# esplash.net
KiCad netlist of a schematic drawn in EAGLE
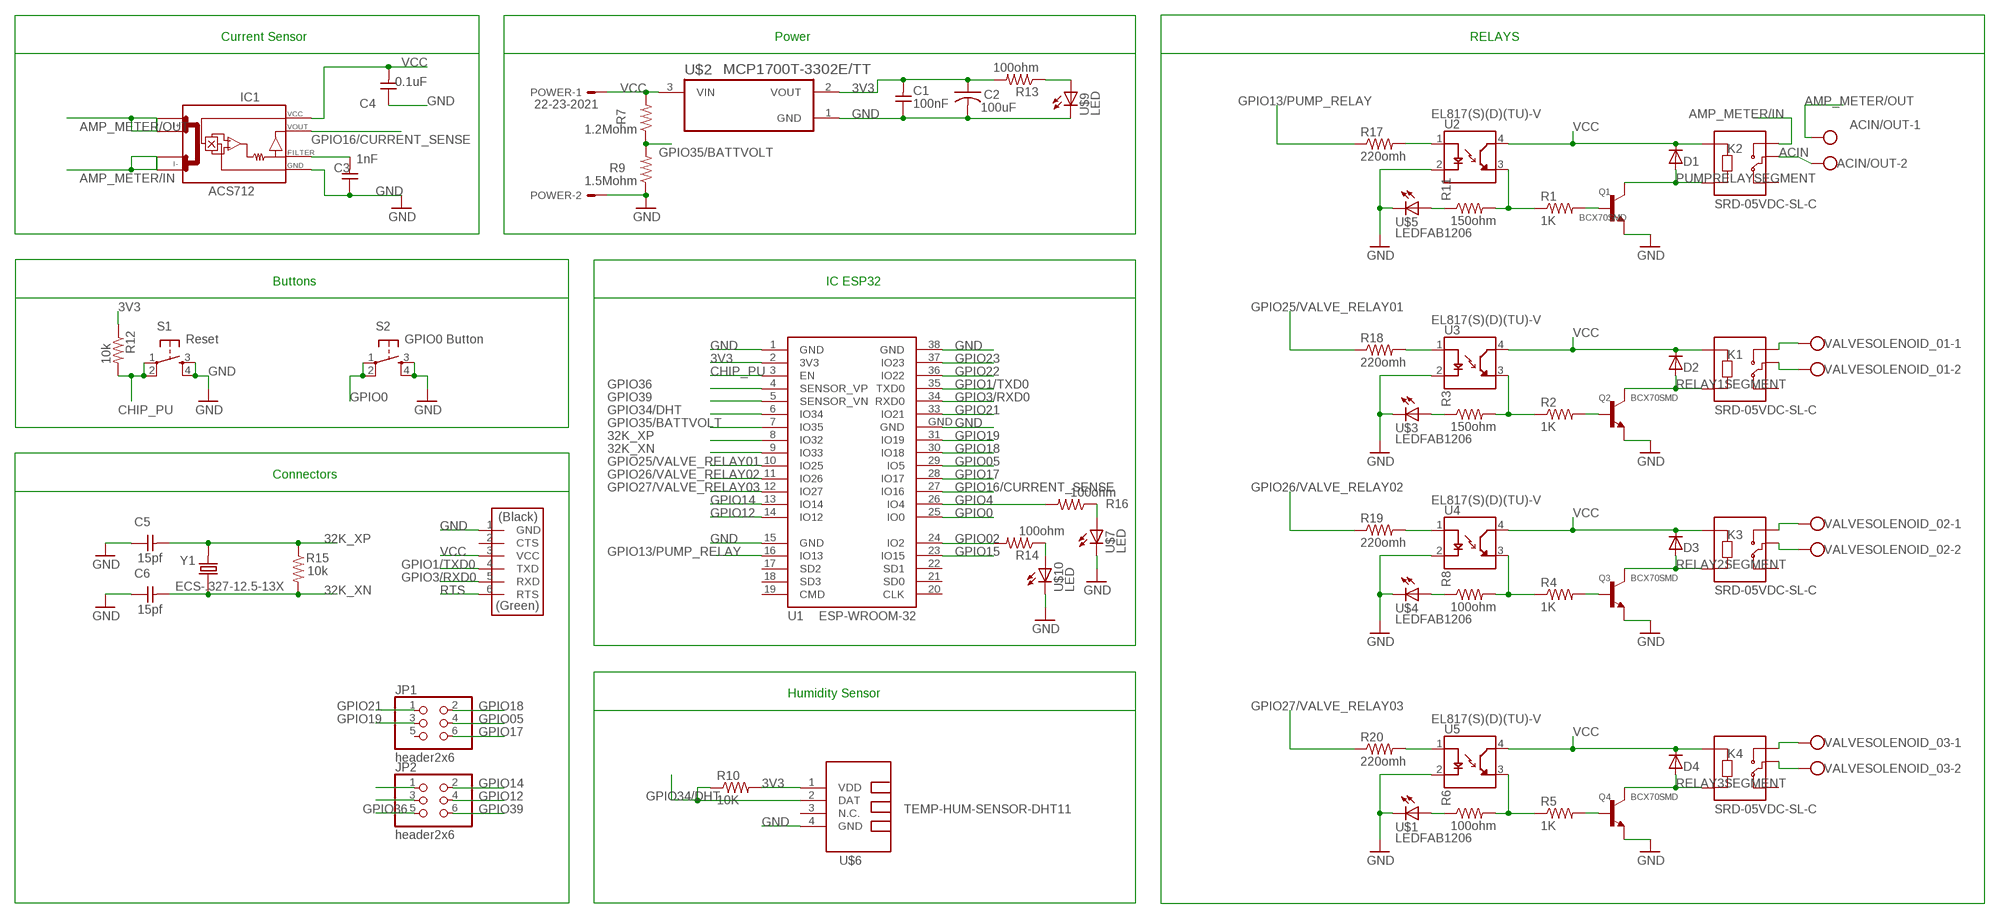
[diagram p0: schematic, sheet 1]

(export (version "E")
  (design (tool "Eeschema 10.0.6"))
  (components
    (comp (ref "ACIN/OUT")
      (value "W237-102")
      (footprint "eagle-import:W237-102")
      (fields (field (name "MPN") "237-102"))
      (libsource (lib "eagle-import") (part "W237-102"))
    )
    (comp (ref "C1")
      (value "100nF")
      (footprint "eagle-import:C1206FAB")
      (libsource (lib "eagle-import") (part "CAP-UNPOLARIZEDFAB"))
    )
    (comp (ref "C2")
      (value "100uF")
      (footprint "eagle-import:C1206FAB")
      (libsource (lib "eagle-import") (part "CAP-US1206FAB"))
    )
    (comp (ref "C3")
      (value "1nF")
      (footprint "eagle-import:C1206FAB")
      (libsource (lib "eagle-import") (part "CAP-UNPOLARIZEDFAB"))
    )
    (comp (ref "C4")
      (value "0.1uF")
      (footprint "eagle-import:C1206FAB")
      (libsource (lib "eagle-import") (part "CAP-UNPOLARIZEDFAB"))
    )
    (comp (ref "C5")
      (value "15pf")
      (footprint "eagle-import:C1206FAB")
      (libsource (lib "eagle-import") (part "CAP-UNPOLARIZEDFAB"))
    )
    (comp (ref "C6")
      (value "15pf")
      (footprint "eagle-import:C1206FAB")
      (libsource (lib "eagle-import") (part "CAP-UNPOLARIZEDFAB"))
    )
    (comp (ref "D1")
      (value "DIODESOD123")
      (footprint "eagle-import:SOD123")
      (libsource (lib "eagle-import") (part "DIODESOD123"))
    )
    (comp (ref "D2")
      (value "DIODESOD123")
      (footprint "eagle-import:SOD123")
      (libsource (lib "eagle-import") (part "DIODESOD123"))
    )
    (comp (ref "D3")
      (value "DIODESOD123")
      (footprint "eagle-import:SOD123")
      (libsource (lib "eagle-import") (part "DIODESOD123"))
    )
    (comp (ref "D4")
      (value "DIODESOD123")
      (footprint "eagle-import:SOD123")
      (libsource (lib "eagle-import") (part "DIODESOD123"))
    )
    (comp (ref "IC1")
      (value "ACS712")
      (footprint "eagle-import:SO08")
      (libsource (lib "eagle-import") (part "ACS712"))
    )
    (comp (ref "JP1")
      (value "header2x6")
      (footprint "eagle-import:2X03")
      (libsource (lib "eagle-import") (part "PINHD-2X3"))
    )
    (comp (ref "JP2")
      (value "header2x6")
      (footprint "eagle-import:2X03")
      (libsource (lib "eagle-import") (part "PINHD-2X3"))
    )
    (comp (ref "K1")
      (value "SRD-05VDC-SL-C")
      (footprint "eagle-import:RELAY_SRD-05VDC-SL-C")
      (fields (field (name "MF") "Songle Relay"))
      (libsource (lib "eagle-import") (part "SRD-05VDC-SL-C"))
    )
    (comp (ref "K2")
      (value "SRD-05VDC-SL-C")
      (footprint "eagle-import:RELAY_SRD-05VDC-SL-C")
      (fields (field (name "MF") "Songle Relay"))
      (libsource (lib "eagle-import") (part "SRD-05VDC-SL-C"))
    )
    (comp (ref "K3")
      (value "SRD-05VDC-SL-C")
      (footprint "eagle-import:RELAY_SRD-05VDC-SL-C")
      (fields (field (name "MF") "Songle Relay"))
      (libsource (lib "eagle-import") (part "SRD-05VDC-SL-C"))
    )
    (comp (ref "K4")
      (value "SRD-05VDC-SL-C")
      (footprint "eagle-import:RELAY_SRD-05VDC-SL-C")
      (fields (field (name "MF") "Songle Relay"))
      (libsource (lib "eagle-import") (part "SRD-05VDC-SL-C"))
    )
    (comp (ref "POWER")
      (value "22-23-2021")
      (footprint "eagle-import:22-23-2021")
      (fields (field (name "MF") "MOLEX"))
      (libsource (lib "eagle-import") (part "22-23-2021"))
    )
    (comp (ref "Q1")
      (value "BCX70SMD")
      (footprint "eagle-import:SOT23")
      (libsource (lib "eagle-import") (part "BCX70SMD"))
    )
    (comp (ref "Q2")
      (value "BCX70SMD")
      (footprint "eagle-import:SOT23")
      (libsource (lib "eagle-import") (part "BCX70SMD"))
    )
    (comp (ref "Q3")
      (value "BCX70SMD")
      (footprint "eagle-import:SOT23")
      (libsource (lib "eagle-import") (part "BCX70SMD"))
    )
    (comp (ref "Q4")
      (value "BCX70SMD")
      (footprint "eagle-import:SOT23")
      (libsource (lib "eagle-import") (part "BCX70SMD"))
    )
    (comp (ref "R1")
      (value "1K")
      (footprint "eagle-import:R1206FAB")
      (libsource (lib "eagle-import") (part "RES-US1206FAB"))
    )
    (comp (ref "R2")
      (value "1K")
      (footprint "eagle-import:R1206FAB")
      (libsource (lib "eagle-import") (part "RES-US1206FAB"))
    )
    (comp (ref "R3")
      (value "150ohm")
      (footprint "eagle-import:R1206FAB")
      (libsource (lib "eagle-import") (part "RES-US1206FAB"))
    )
    (comp (ref "R4")
      (value "1K")
      (footprint "eagle-import:R1206FAB")
      (libsource (lib "eagle-import") (part "RES-US1206FAB"))
    )
    (comp (ref "R5")
      (value "1K")
      (footprint "eagle-import:R1206FAB")
      (libsource (lib "eagle-import") (part "RES-US1206FAB"))
    )
    (comp (ref "R6")
      (value "100ohm")
      (footprint "eagle-import:R1206FAB")
      (libsource (lib "eagle-import") (part "RES-US1206FAB"))
    )
    (comp (ref "R7")
      (value "1.2Mohm")
      (footprint "eagle-import:R1206FAB")
      (libsource (lib "eagle-import") (part "RES-US1206FAB"))
    )
    (comp (ref "R8")
      (value "100ohm")
      (footprint "eagle-import:R1206FAB")
      (libsource (lib "eagle-import") (part "RES-US1206FAB"))
    )
    (comp (ref "R9")
      (value "1.5Mohm")
      (footprint "eagle-import:R1206FAB")
      (libsource (lib "eagle-import") (part "RES-US1206FAB"))
    )
    (comp (ref "R10")
      (value "10K")
      (footprint "eagle-import:R1206FAB")
      (libsource (lib "eagle-import") (part "RES-US1206FAB"))
    )
    (comp (ref "R11")
      (value "150ohm")
      (footprint "eagle-import:R1206FAB")
      (libsource (lib "eagle-import") (part "RES-US1206FAB"))
    )
    (comp (ref "R12")
      (value "10k")
      (footprint "eagle-import:R1206")
      (libsource (lib "eagle-import") (part "RES-US1206"))
    )
    (comp (ref "R13")
      (value "100ohm")
      (footprint "eagle-import:R1206")
      (libsource (lib "eagle-import") (part "RES-US1206"))
    )
    (comp (ref "R14")
      (value "100ohm")
      (footprint "eagle-import:R1206")
      (libsource (lib "eagle-import") (part "RES-US1206"))
    )
    (comp (ref "R15")
      (value "10k")
      (footprint "eagle-import:R1206")
      (libsource (lib "eagle-import") (part "RES-US1206"))
    )
    (comp (ref "R16")
      (value "100ohm")
      (footprint "eagle-import:R1206")
      (libsource (lib "eagle-import") (part "RES-US1206"))
    )
    (comp (ref "R17")
      (value "220omh")
      (footprint "eagle-import:R1206FAB")
      (libsource (lib "eagle-import") (part "RES-US1206FAB"))
    )
    (comp (ref "R18")
      (value "220omh")
      (footprint "eagle-import:R1206FAB")
      (libsource (lib "eagle-import") (part "RES-US1206FAB"))
    )
    (comp (ref "R19")
      (value "220omh")
      (footprint "eagle-import:R1206FAB")
      (libsource (lib "eagle-import") (part "RES-US1206FAB"))
    )
    (comp (ref "R20")
      (value "220omh")
      (footprint "eagle-import:R1206FAB")
      (libsource (lib "eagle-import") (part "RES-US1206FAB"))
    )
    (comp (ref "RTS")
      (value "FTDI-SMD-HEADER")
      (footprint "eagle-import:1X06SMD")
      (libsource (lib "eagle-import") (part "FTDI-SMD-HEADER"))
    )
    (comp (ref "S1")
      (value "Reset")
      (footprint "eagle-import:6MM_SWITCH")
      (libsource (lib "eagle-import") (part "6MM_SWITCH6MM_SWITCH"))
    )
    (comp (ref "S2")
      (value "GPIO0 Button")
      (footprint "eagle-import:6MM_SWITCH")
      (libsource (lib "eagle-import") (part "6MM_SWITCH6MM_SWITCH"))
    )
    (comp (ref "U$1")
      (value "LEDFAB1206")
      (footprint "eagle-import:LED1206FAB")
      (libsource (lib "eagle-import") (part "LEDFAB1206"))
    )
    (comp (ref "U$2")
      (value "MCP1700T-3302E/TT")
      (footprint "eagle-import:SOT95P237X112-3N")
      (fields (field (name "MF") "Microchip Technology"))
      (libsource (lib "eagle-import") (part "MCP1700T-3302E/TT"))
    )
    (comp (ref "U$3")
      (value "LEDFAB1206")
      (footprint "eagle-import:LED1206FAB")
      (libsource (lib "eagle-import") (part "LEDFAB1206"))
    )
    (comp (ref "U$4")
      (value "LEDFAB1206")
      (footprint "eagle-import:LED1206FAB")
      (libsource (lib "eagle-import") (part "LEDFAB1206"))
    )
    (comp (ref "U$5")
      (value "LEDFAB1206")
      (footprint "eagle-import:LED1206FAB")
      (libsource (lib "eagle-import") (part "LEDFAB1206"))
    )
    (comp (ref "U$6")
      (value "TEMP-HUM-SENSOR-DHT11")
      (footprint "eagle-import:TEMP-HUM-SENSOR-DHT11")
      (libsource (lib "eagle-import") (part "TEMP-HUM-SENSOR-DHT11"))
    )
    (comp (ref "U$7")
      (value "LED")
      (footprint "eagle-import:LED1206")
      (libsource (lib "eagle-import") (part "LED"))
    )
    (comp (ref "U$9")
      (value "LED")
      (footprint "eagle-import:LED1206")
      (libsource (lib "eagle-import") (part "LED"))
    )
    (comp (ref "U$10")
      (value "LED")
      (footprint "eagle-import:LED1206")
      (libsource (lib "eagle-import") (part "LED"))
    )
    (comp (ref "U1")
      (value "ESP-WROOM-32")
      (footprint "eagle-import:ESP-WROOM-32")
      (libsource (lib "eagle-import") (part "ESP-WROOM-32"))
    )
    (comp (ref "U2")
      (value "EL817(S)(D)(TU)-V")
      (footprint "eagle-import:SOIC254P1030X460-4N")
      (fields (field (name "MF") "Everlight Electronics"))
      (libsource (lib "eagle-import") (part "EL817(S)(D)(TU)-V"))
    )
    (comp (ref "U3")
      (value "EL817(S)(D)(TU)-V")
      (footprint "eagle-import:SOIC254P1030X460-4N")
      (fields (field (name "MF") "Everlight Electronics"))
      (libsource (lib "eagle-import") (part "EL817(S)(D)(TU)-V"))
    )
    (comp (ref "U4")
      (value "EL817(S)(D)(TU)-V")
      (footprint "eagle-import:SOIC254P1030X460-4N")
      (fields (field (name "MF") "Everlight Electronics"))
      (libsource (lib "eagle-import") (part "EL817(S)(D)(TU)-V"))
    )
    (comp (ref "U5")
      (value "EL817(S)(D)(TU)-V")
      (footprint "eagle-import:SOIC254P1030X460-4N")
      (fields (field (name "MF") "Everlight Electronics"))
      (libsource (lib "eagle-import") (part "EL817(S)(D)(TU)-V"))
    )
    (comp (ref "VALVESOLENOID_01")
      (value "W237-102")
      (footprint "eagle-import:W237-102")
      (fields (field (name "MPN") "237-102"))
      (libsource (lib "eagle-import") (part "W237-102"))
    )
    (comp (ref "VALVESOLENOID_02")
      (value "W237-102")
      (footprint "eagle-import:W237-102")
      (fields (field (name "MPN") "237-102"))
      (libsource (lib "eagle-import") (part "W237-102"))
    )
    (comp (ref "VALVESOLENOID_03")
      (value "W237-102")
      (footprint "eagle-import:W237-102")
      (fields (field (name "MPN") "237-102"))
      (libsource (lib "eagle-import") (part "W237-102"))
    )
    (comp (ref "Y1")
      (value "ECS-.327-12.5-13X")
      (footprint "eagle-import:XTAL_ECS-.327-12.5-13X")
      (fields (field (name "MF") "ECS Inc."))
      (libsource (lib "eagle-import") (part "ECS-.327-12.5-13X"))
    )
  )
  (nets
    (net (code "1") (name "/3V3") (class "Default")
      (node (ref "C1") (pin "2") (pinfunction "2_2") (pintype "passive"))
      (node (ref "C2") (pin "1") (pinfunction "1_1") (pintype "passive"))
      (node (ref "R10") (pin "2") (pinfunction "2_2") (pintype "passive"))
      (node (ref "R12") (pin "1") (pinfunction "1_1") (pintype "passive"))
      (node (ref "R13") (pin "2") (pinfunction "2_2") (pintype "passive"))
      (node (ref "U$2") (pin "2") (pinfunction "VOUT_2") (pintype "output"))
      (node (ref "U$6") (pin "1") (pinfunction "VDD_1") (pintype "power_in"))
      (node (ref "U1") (pin "2") (pinfunction "3V3_2") (pintype "power_in"))
    )
    (net (code "2") (name "/32K_XN") (class "Default")
      (node (ref "C6") (pin "2") (pinfunction "2_2") (pintype "passive"))
      (node (ref "R15") (pin "2") (pinfunction "2_2") (pintype "passive"))
      (node (ref "U1") (pin "9") (pinfunction "IO33_9") (pintype "bidirectional"))
      (node (ref "Y1") (pin "1") (pinfunction "1_1") (pintype "passive"))
    )
    (net (code "3") (name "/32K_XP") (class "Default")
      (node (ref "C5") (pin "2") (pinfunction "2_2") (pintype "passive"))
      (node (ref "R15") (pin "1") (pinfunction "1_1") (pintype "passive"))
      (node (ref "U1") (pin "8") (pinfunction "IO32_8") (pintype "bidirectional"))
      (node (ref "Y1") (pin "2") (pinfunction "2_2") (pintype "passive"))
    )
    (net (code "4") (name "/ACIN") (class "Default")
      (node (ref "ACIN/OUT") (pin "2") (pinfunction "KL_2") (pintype "passive"))
      (node (ref "K2") (pin "COM") (pinfunction "COM_COM") (pintype "passive"))
    )
    (net (code "5") (name "/AMP_METER{slash}IN") (class "Default")
      (node (ref "IC1") (pin "3") (pinfunction "I-_0_3") (pintype "bidirectional"))
      (node (ref "IC1") (pin "4") (pinfunction "I-_1_4") (pintype "bidirectional"))
      (node (ref "K2") (pin "NO") (pinfunction "NO_NO") (pintype "passive"))
    )
    (net (code "6") (name "/AMP_METER{slash}OUT") (class "Default")
      (node (ref "ACIN/OUT") (pin "1") (pinfunction "KL_1") (pintype "passive"))
      (node (ref "IC1") (pin "1") (pinfunction "I+_0_1") (pintype "bidirectional"))
      (node (ref "IC1") (pin "2") (pinfunction "I+_1_2") (pintype "bidirectional"))
    )
    (net (code "7") (name "/CHIP_PU") (class "Default")
      (node (ref "R12") (pin "2") (pinfunction "2_2") (pintype "passive"))
      (node (ref "S1") (pin "1") (pinfunction "P_1") (pintype "passive"))
      (node (ref "S1") (pin "2") (pinfunction "P1_2") (pintype "passive"))
      (node (ref "U1") (pin "3") (pinfunction "EN_3") (pintype "input"))
    )
    (net (code "8") (name "/GPIO0") (class "Default")
      (node (ref "S2") (pin "1") (pinfunction "P_1") (pintype "passive"))
      (node (ref "S2") (pin "2") (pinfunction "P1_2") (pintype "passive"))
      (node (ref "U1") (pin "25") (pinfunction "IO0_25") (pintype "bidirectional"))
    )
    (net (code "9") (name "/GPIO1{slash}TXD0") (class "Default")
      (node (ref "RTS") (pin "4") (pinfunction "TXD_4") (pintype "bidirectional"))
      (node (ref "U1") (pin "35") (pinfunction "TXD0_35") (pintype "bidirectional"))
    )
    (net (code "10") (name "/GPIO02") (class "Default")
      (node (ref "R14") (pin "2") (pinfunction "2_2") (pintype "passive"))
      (node (ref "U1") (pin "24") (pinfunction "IO2_24") (pintype "bidirectional"))
    )
    (net (code "11") (name "/GPIO3{slash}RXD0") (class "Default")
      (node (ref "RTS") (pin "5") (pinfunction "RXD_5") (pintype "bidirectional"))
      (node (ref "U1") (pin "34") (pinfunction "RXD0_34") (pintype "bidirectional"))
    )
    (net (code "12") (name "/GPIO4") (class "Default")
      (node (ref "R16") (pin "2") (pinfunction "2_2") (pintype "passive"))
      (node (ref "U1") (pin "26") (pinfunction "IO4_26") (pintype "bidirectional"))
    )
    (net (code "13") (name "/GPIO05") (class "Default")
      (node (ref "JP1") (pin "4") (pinfunction "4_4") (pintype "passive"))
      (node (ref "U1") (pin "29") (pinfunction "IO5_29") (pintype "bidirectional"))
    )
    (net (code "14") (name "/GPIO12") (class "Default")
      (node (ref "JP2") (pin "4") (pinfunction "4_4") (pintype "passive"))
      (node (ref "U1") (pin "14") (pinfunction "IO12_14") (pintype "bidirectional"))
    )
    (net (code "15") (name "/GPIO13{slash}PUMP_RELAY") (class "Default")
      (node (ref "R17") (pin "1") (pinfunction "1_1") (pintype "passive"))
      (node (ref "U1") (pin "16") (pinfunction "IO13_16") (pintype "bidirectional"))
    )
    (net (code "16") (name "/GPIO14") (class "Default")
      (node (ref "JP2") (pin "2") (pinfunction "2_2") (pintype "passive"))
      (node (ref "U1") (pin "13") (pinfunction "IO14_13") (pintype "bidirectional"))
    )
    (net (code "17") (name "/GPIO15") (class "Default")
      (node (ref "U1") (pin "23") (pinfunction "IO15_23") (pintype "bidirectional"))
    )
    (net (code "18") (name "/GPIO16{slash}CURRENT_SENSE") (class "Default")
      (node (ref "IC1") (pin "7") (pinfunction "VOUT_7") (pintype "output"))
      (node (ref "U1") (pin "27") (pinfunction "IO16_27") (pintype "bidirectional"))
    )
    (net (code "19") (name "/GPIO17") (class "Default")
      (node (ref "JP1") (pin "6") (pinfunction "6_6") (pintype "passive"))
      (node (ref "U1") (pin "28") (pinfunction "IO17_28") (pintype "bidirectional"))
    )
    (net (code "20") (name "/GPIO18") (class "Default")
      (node (ref "JP1") (pin "2") (pinfunction "2_2") (pintype "passive"))
      (node (ref "U1") (pin "30") (pinfunction "IO18_30") (pintype "bidirectional"))
    )
    (net (code "21") (name "/GPIO19") (class "Default")
      (node (ref "JP1") (pin "3") (pinfunction "3_3") (pintype "passive"))
      (node (ref "U1") (pin "31") (pinfunction "IO19_31") (pintype "bidirectional"))
    )
    (net (code "22") (name "/GPIO21") (class "Default")
      (node (ref "JP1") (pin "1") (pinfunction "1_1") (pintype "passive"))
      (node (ref "U1") (pin "33") (pinfunction "IO21_33") (pintype "bidirectional"))
    )
    (net (code "23") (name "/GPIO22") (class "Default")
      (node (ref "U1") (pin "36") (pinfunction "IO22_36") (pintype "bidirectional"))
    )
    (net (code "24") (name "/GPIO23") (class "Default")
      (node (ref "U1") (pin "37") (pinfunction "IO23_37") (pintype "bidirectional"))
    )
    (net (code "25") (name "/GPIO25{slash}VALVE_RELAY01") (class "Default")
      (node (ref "R18") (pin "1") (pinfunction "1_1") (pintype "passive"))
      (node (ref "U1") (pin "10") (pinfunction "IO25_10") (pintype "bidirectional"))
    )
    (net (code "26") (name "/GPIO26{slash}VALVE_RELAY02") (class "Default")
      (node (ref "R19") (pin "1") (pinfunction "1_1") (pintype "passive"))
      (node (ref "U1") (pin "11") (pinfunction "IO26_11") (pintype "bidirectional"))
    )
    (net (code "27") (name "/GPIO27{slash}VALVE_RELAY03") (class "Default")
      (node (ref "R20") (pin "1") (pinfunction "1_1") (pintype "passive"))
      (node (ref "U1") (pin "12") (pinfunction "IO27_12") (pintype "bidirectional"))
    )
    (net (code "28") (name "/GPIO34{slash}DHT") (class "Default")
      (node (ref "R10") (pin "1") (pinfunction "1_1") (pintype "passive"))
      (node (ref "U$6") (pin "2") (pinfunction "DAT_2") (pintype "bidirectional"))
      (node (ref "U1") (pin "6") (pinfunction "IO34_6") (pintype "bidirectional"))
    )
    (net (code "29") (name "/GPIO35{slash}BATTVOLT") (class "Default")
      (node (ref "R7") (pin "1") (pinfunction "1_1") (pintype "passive"))
      (node (ref "R9") (pin "2") (pinfunction "2_2") (pintype "passive"))
      (node (ref "U1") (pin "7") (pinfunction "IO35_7") (pintype "bidirectional"))
    )
    (net (code "30") (name "/GPIO36") (class "Default")
      (node (ref "JP2") (pin "5") (pinfunction "5_5") (pintype "passive"))
      (node (ref "U1") (pin "4") (pinfunction "SENSOR_VP_4") (pintype "bidirectional"))
    )
    (net (code "31") (name "/GPIO39") (class "Default")
      (node (ref "JP2") (pin "6") (pinfunction "6_6") (pintype "passive"))
      (node (ref "U1") (pin "5") (pinfunction "SENSOR_VN_5") (pintype "bidirectional"))
    )
    (net (code "32") (name "/PUMPRELAYSEGMENT") (class "Default")
      (node (ref "D1") (pin "ANODE") (pinfunction "A_ANODE") (pintype "passive"))
      (node (ref "K2") (pin "A2") (pinfunction "A2_A2") (pintype "passive"))
      (node (ref "Q1") (pin "3") (pinfunction "C_3") (pintype "passive"))
    )
    (net (code "33") (name "/RELAY1SEGMENT") (class "Default")
      (node (ref "D2") (pin "ANODE") (pinfunction "A_ANODE") (pintype "passive"))
      (node (ref "K1") (pin "A2") (pinfunction "A2_A2") (pintype "passive"))
      (node (ref "Q2") (pin "3") (pinfunction "C_3") (pintype "passive"))
    )
    (net (code "34") (name "/RELAY2SEGMENT") (class "Default")
      (node (ref "D3") (pin "ANODE") (pinfunction "A_ANODE") (pintype "passive"))
      (node (ref "K3") (pin "A2") (pinfunction "A2_A2") (pintype "passive"))
      (node (ref "Q3") (pin "3") (pinfunction "C_3") (pintype "passive"))
    )
    (net (code "35") (name "/RELAY3SEGMENT") (class "Default")
      (node (ref "D4") (pin "ANODE") (pinfunction "A_ANODE") (pintype "passive"))
      (node (ref "K4") (pin "A2") (pinfunction "A2_A2") (pintype "passive"))
      (node (ref "Q4") (pin "3") (pinfunction "C_3") (pintype "passive"))
    )
    (net (code "36") (name "/RTS") (class "Default")
      (node (ref "RTS") (pin "6") (pinfunction "RTS_6") (pintype "bidirectional"))
    )
    (net (code "37") (name "/VCC") (class "Default")
      (node (ref "C4") (pin "2") (pinfunction "2_2") (pintype "passive"))
      (node (ref "D1") (pin "CATHODE") (pinfunction "C_CATHODE") (pintype "passive"))
      (node (ref "D2") (pin "CATHODE") (pinfunction "C_CATHODE") (pintype "passive"))
      (node (ref "D3") (pin "CATHODE") (pinfunction "C_CATHODE") (pintype "passive"))
      (node (ref "D4") (pin "CATHODE") (pinfunction "C_CATHODE") (pintype "passive"))
      (node (ref "IC1") (pin "8") (pinfunction "VCC_8") (pintype "power_in"))
      (node (ref "K1") (pin "A1") (pinfunction "A1_A1") (pintype "passive"))
      (node (ref "K2") (pin "A1") (pinfunction "A1_A1") (pintype "passive"))
      (node (ref "K3") (pin "A1") (pinfunction "A1_A1") (pintype "passive"))
      (node (ref "K4") (pin "A1") (pinfunction "A1_A1") (pintype "passive"))
      (node (ref "POWER") (pin "1") (pinfunction "S_1") (pintype "passive"))
      (node (ref "R7") (pin "2") (pinfunction "2_2") (pintype "passive"))
      (node (ref "RTS") (pin "3") (pinfunction "VCC_3") (pintype "bidirectional"))
      (node (ref "U$2") (pin "3") (pinfunction "VIN_3") (pintype "input"))
      (node (ref "U2") (pin "4") (pinfunction "CT_4") (pintype "passive"))
      (node (ref "U3") (pin "4") (pinfunction "CT_4") (pintype "passive"))
      (node (ref "U4") (pin "4") (pinfunction "CT_4") (pintype "passive"))
      (node (ref "U5") (pin "4") (pinfunction "CT_4") (pintype "passive"))
    )
    (net (code "38") (name "GND") (class "Default")
      (node (ref "C1") (pin "1") (pinfunction "1_1") (pintype "passive"))
      (node (ref "C2") (pin "2") (pinfunction "2_2") (pintype "passive"))
      (node (ref "C3") (pin "1") (pinfunction "1_1") (pintype "passive"))
      (node (ref "C4") (pin "1") (pinfunction "1_1") (pintype "passive"))
      (node (ref "C5") (pin "1") (pinfunction "1_1") (pintype "passive"))
      (node (ref "C6") (pin "1") (pinfunction "1_1") (pintype "passive"))
      (node (ref "IC1") (pin "5") (pinfunction "GND_5") (pintype "power_in"))
      (node (ref "POWER") (pin "2") (pinfunction "S_2") (pintype "passive"))
      (node (ref "Q1") (pin "2") (pinfunction "E_2") (pintype "passive"))
      (node (ref "Q2") (pin "2") (pinfunction "E_2") (pintype "passive"))
      (node (ref "Q3") (pin "2") (pinfunction "E_2") (pintype "passive"))
      (node (ref "Q4") (pin "2") (pinfunction "E_2") (pintype "passive"))
      (node (ref "R9") (pin "1") (pinfunction "1_1") (pintype "passive"))
      (node (ref "RTS") (pin "1") (pinfunction "GND_1") (pintype "bidirectional"))
      (node (ref "S1") (pin "3") (pinfunction "S_3") (pintype "passive"))
      (node (ref "S1") (pin "4") (pinfunction "S1_4") (pintype "passive"))
      (node (ref "S2") (pin "3") (pinfunction "S_3") (pintype "passive"))
      (node (ref "S2") (pin "4") (pinfunction "S1_4") (pintype "passive"))
      (node (ref "U$1") (pin "2") (pinfunction "C_2") (pintype "passive"))
      (node (ref "U$10") (pin "2") (pinfunction "C_2") (pintype "passive"))
      (node (ref "U$2") (pin "1") (pinfunction "GND_1") (pintype "power_in"))
      (node (ref "U$3") (pin "2") (pinfunction "C_2") (pintype "passive"))
      (node (ref "U$4") (pin "2") (pinfunction "C_2") (pintype "passive"))
      (node (ref "U$5") (pin "2") (pinfunction "C_2") (pintype "passive"))
      (node (ref "U$6") (pin "4") (pinfunction "GND_4") (pintype "power_in"))
      (node (ref "U$7") (pin "2") (pinfunction "C_2") (pintype "passive"))
      (node (ref "U$9") (pin "2") (pinfunction "C_2") (pintype "passive"))
      (node (ref "U1") (pin "1") (pinfunction "GND_1") (pintype "power_in"))
      (node (ref "U1") (pin "15") (pinfunction "GND_15") (pintype "power_in"))
      (node (ref "U1") (pin "38") (pinfunction "GND_38") (pintype "power_in"))
      (node (ref "U1") (pin "GND") (pinfunction "GND_GND") (pintype "power_in"))
      (node (ref "U2") (pin "2") (pinfunction "C_2") (pintype "passive"))
      (node (ref "U3") (pin "2") (pinfunction "C_2") (pintype "passive"))
      (node (ref "U4") (pin "2") (pinfunction "C_2") (pintype "passive"))
      (node (ref "U5") (pin "2") (pinfunction "C_2") (pintype "passive"))
    )
    (net (code "39") (name "Net-(IC1-FILTER)") (class "Default")
      (node (ref "C3") (pin "2") (pinfunction "2_2") (pintype "passive"))
      (node (ref "IC1") (pin "6") (pinfunction "FILTER_6") (pintype "bidirectional"))
    )
    (net (code "40") (name "Net-(Q1-B)") (class "Default")
      (node (ref "Q1") (pin "1") (pinfunction "B_1") (pintype "passive"))
      (node (ref "R1") (pin "2") (pinfunction "2_2") (pintype "passive"))
    )
    (net (code "41") (name "Net-(Q2-B)") (class "Default")
      (node (ref "Q2") (pin "1") (pinfunction "B_1") (pintype "passive"))
      (node (ref "R2") (pin "2") (pinfunction "2_2") (pintype "passive"))
    )
    (net (code "42") (name "Net-(Q3-B)") (class "Default")
      (node (ref "Q3") (pin "1") (pinfunction "B_1") (pintype "passive"))
      (node (ref "R4") (pin "2") (pinfunction "2_2") (pintype "passive"))
    )
    (net (code "43") (name "Net-(Q4-B)") (class "Default")
      (node (ref "Q4") (pin "1") (pinfunction "B_1") (pintype "passive"))
      (node (ref "R5") (pin "2") (pinfunction "2_2") (pintype "passive"))
    )
    (net (code "44") (name "Net-(U$1-A)") (class "Default")
      (node (ref "R6") (pin "1") (pinfunction "1_1") (pintype "passive"))
      (node (ref "U$1") (pin "1") (pinfunction "A_1") (pintype "passive"))
    )
    (net (code "45") (name "Net-(U$3-A)") (class "Default")
      (node (ref "R3") (pin "1") (pinfunction "1_1") (pintype "passive"))
      (node (ref "U$3") (pin "1") (pinfunction "A_1") (pintype "passive"))
    )
    (net (code "46") (name "Net-(U$4-A)") (class "Default")
      (node (ref "R8") (pin "1") (pinfunction "1_1") (pintype "passive"))
      (node (ref "U$4") (pin "1") (pinfunction "A_1") (pintype "passive"))
    )
    (net (code "47") (name "Net-(U$5-A)") (class "Default")
      (node (ref "R11") (pin "1") (pinfunction "1_1") (pintype "passive"))
      (node (ref "U$5") (pin "1") (pinfunction "A_1") (pintype "passive"))
    )
    (net (code "48") (name "Net-(U$7-A)") (class "Default")
      (node (ref "R16") (pin "1") (pinfunction "1_1") (pintype "passive"))
      (node (ref "U$7") (pin "1") (pinfunction "A_1") (pintype "passive"))
    )
    (net (code "49") (name "Net-(U$9-A)") (class "Default")
      (node (ref "R13") (pin "1") (pinfunction "1_1") (pintype "passive"))
      (node (ref "U$9") (pin "1") (pinfunction "A_1") (pintype "passive"))
    )
    (net (code "50") (name "Net-(U$10-A)") (class "Default")
      (node (ref "R14") (pin "1") (pinfunction "1_1") (pintype "passive"))
      (node (ref "U$10") (pin "1") (pinfunction "A_1") (pintype "passive"))
    )
    (net (code "51") (name "Net-(U2-A)") (class "Default")
      (node (ref "R17") (pin "2") (pinfunction "2_2") (pintype "passive"))
      (node (ref "U2") (pin "1") (pinfunction "A_1") (pintype "passive"))
    )
    (net (code "52") (name "Net-(U2-ET)") (class "Default")
      (node (ref "R1") (pin "1") (pinfunction "1_1") (pintype "passive"))
      (node (ref "R11") (pin "2") (pinfunction "2_2") (pintype "passive"))
      (node (ref "U2") (pin "3") (pinfunction "ET_3") (pintype "passive"))
    )
    (net (code "53") (name "Net-(U3-A)") (class "Default")
      (node (ref "R18") (pin "2") (pinfunction "2_2") (pintype "passive"))
      (node (ref "U3") (pin "1") (pinfunction "A_1") (pintype "passive"))
    )
    (net (code "54") (name "Net-(U3-ET)") (class "Default")
      (node (ref "R2") (pin "1") (pinfunction "1_1") (pintype "passive"))
      (node (ref "R3") (pin "2") (pinfunction "2_2") (pintype "passive"))
      (node (ref "U3") (pin "3") (pinfunction "ET_3") (pintype "passive"))
    )
    (net (code "55") (name "Net-(U4-A)") (class "Default")
      (node (ref "R19") (pin "2") (pinfunction "2_2") (pintype "passive"))
      (node (ref "U4") (pin "1") (pinfunction "A_1") (pintype "passive"))
    )
    (net (code "56") (name "Net-(U4-ET)") (class "Default")
      (node (ref "R4") (pin "1") (pinfunction "1_1") (pintype "passive"))
      (node (ref "R8") (pin "2") (pinfunction "2_2") (pintype "passive"))
      (node (ref "U4") (pin "3") (pinfunction "ET_3") (pintype "passive"))
    )
    (net (code "57") (name "Net-(U5-A)") (class "Default")
      (node (ref "R20") (pin "2") (pinfunction "2_2") (pintype "passive"))
      (node (ref "U5") (pin "1") (pinfunction "A_1") (pintype "passive"))
    )
    (net (code "58") (name "Net-(U5-ET)") (class "Default")
      (node (ref "R5") (pin "1") (pinfunction "1_1") (pintype "passive"))
      (node (ref "R6") (pin "2") (pinfunction "2_2") (pintype "passive"))
      (node (ref "U5") (pin "3") (pinfunction "ET_3") (pintype "passive"))
    )
    (net (code "59") (name "Net-(VALVESOLENOID_01A-KL)") (class "Default")
      (node (ref "K1") (pin "NO") (pinfunction "NO_NO") (pintype "passive"))
      (node (ref "VALVESOLENOID_01") (pin "1") (pinfunction "KL_1") (pintype "passive"))
    )
    (net (code "60") (name "Net-(VALVESOLENOID_01B-KL)") (class "Default")
      (node (ref "K1") (pin "COM") (pinfunction "COM_COM") (pintype "passive"))
      (node (ref "VALVESOLENOID_01") (pin "2") (pinfunction "KL_2") (pintype "passive"))
    )
    (net (code "61") (name "Net-(VALVESOLENOID_02A-KL)") (class "Default")
      (node (ref "K3") (pin "NO") (pinfunction "NO_NO") (pintype "passive"))
      (node (ref "VALVESOLENOID_02") (pin "1") (pinfunction "KL_1") (pintype "passive"))
    )
    (net (code "62") (name "Net-(VALVESOLENOID_02B-KL)") (class "Default")
      (node (ref "K3") (pin "COM") (pinfunction "COM_COM") (pintype "passive"))
      (node (ref "VALVESOLENOID_02") (pin "2") (pinfunction "KL_2") (pintype "passive"))
    )
    (net (code "63") (name "Net-(VALVESOLENOID_03A-KL)") (class "Default")
      (node (ref "K4") (pin "NO") (pinfunction "NO_NO") (pintype "passive"))
      (node (ref "VALVESOLENOID_03") (pin "1") (pinfunction "KL_1") (pintype "passive"))
    )
    (net (code "64") (name "Net-(VALVESOLENOID_03B-KL)") (class "Default")
      (node (ref "K4") (pin "COM") (pinfunction "COM_COM") (pintype "passive"))
      (node (ref "VALVESOLENOID_03") (pin "2") (pinfunction "KL_2") (pintype "passive"))
    )
    (net (code "65") (name "unconnected-(JP1-Pad5)") (class "Default")
      (node (ref "JP1") (pin "5") (pinfunction "5_5") (pintype "passive"))
    )
    (net (code "66") (name "unconnected-(JP2-Pad1)") (class "Default")
      (node (ref "JP2") (pin "1") (pinfunction "1_1") (pintype "passive"))
    )
    (net (code "67") (name "unconnected-(JP2-Pad3)") (class "Default")
      (node (ref "JP2") (pin "3") (pinfunction "3_3") (pintype "passive"))
    )
    (net (code "68") (name "unconnected-(K1-PadNC)") (class "Default")
      (node (ref "K1") (pin "NC") (pinfunction "NC_NC") (pintype "passive"))
    )
    (net (code "69") (name "unconnected-(K2-PadNC)") (class "Default")
      (node (ref "K2") (pin "NC") (pinfunction "NC_NC") (pintype "passive"))
    )
    (net (code "70") (name "unconnected-(K3-PadNC)") (class "Default")
      (node (ref "K3") (pin "NC") (pinfunction "NC_NC") (pintype "passive"))
    )
    (net (code "71") (name "unconnected-(K4-PadNC)") (class "Default")
      (node (ref "K4") (pin "NC") (pinfunction "NC_NC") (pintype "passive"))
    )
    (net (code "72") (name "unconnected-(RTS-CTS-Pad2)") (class "Default")
      (node (ref "RTS") (pin "2") (pinfunction "CTS_2") (pintype "bidirectional"))
    )
    (net (code "73") (name "unconnected-(U$6-N.C.-Pad3)") (class "Default")
      (node (ref "U$6") (pin "3") (pinfunction "N.C._3") (pintype "passive"))
    )
    (net (code "74") (name "unconnected-(U1-CLK-Pad20)") (class "Default")
      (node (ref "U1") (pin "20") (pinfunction "CLK_20") (pintype "bidirectional"))
    )
    (net (code "75") (name "unconnected-(U1-CMD-Pad19)") (class "Default")
      (node (ref "U1") (pin "19") (pinfunction "CMD_19") (pintype "bidirectional"))
    )
    (net (code "76") (name "unconnected-(U1-SD0-Pad21)") (class "Default")
      (node (ref "U1") (pin "21") (pinfunction "SD0_21") (pintype "bidirectional"))
    )
    (net (code "77") (name "unconnected-(U1-SD1-Pad22)") (class "Default")
      (node (ref "U1") (pin "22") (pinfunction "SD1_22") (pintype "bidirectional"))
    )
    (net (code "78") (name "unconnected-(U1-SD2-Pad17)") (class "Default")
      (node (ref "U1") (pin "17") (pinfunction "SD2_17") (pintype "bidirectional"))
    )
    (net (code "79") (name "unconnected-(U1-SD3-Pad18)") (class "Default")
      (node (ref "U1") (pin "18") (pinfunction "SD3_18") (pintype "bidirectional"))
    )
  )
)
